# tritiled_v30_xpe.net
KiCad netlist of a schematic drawn in EAGLE
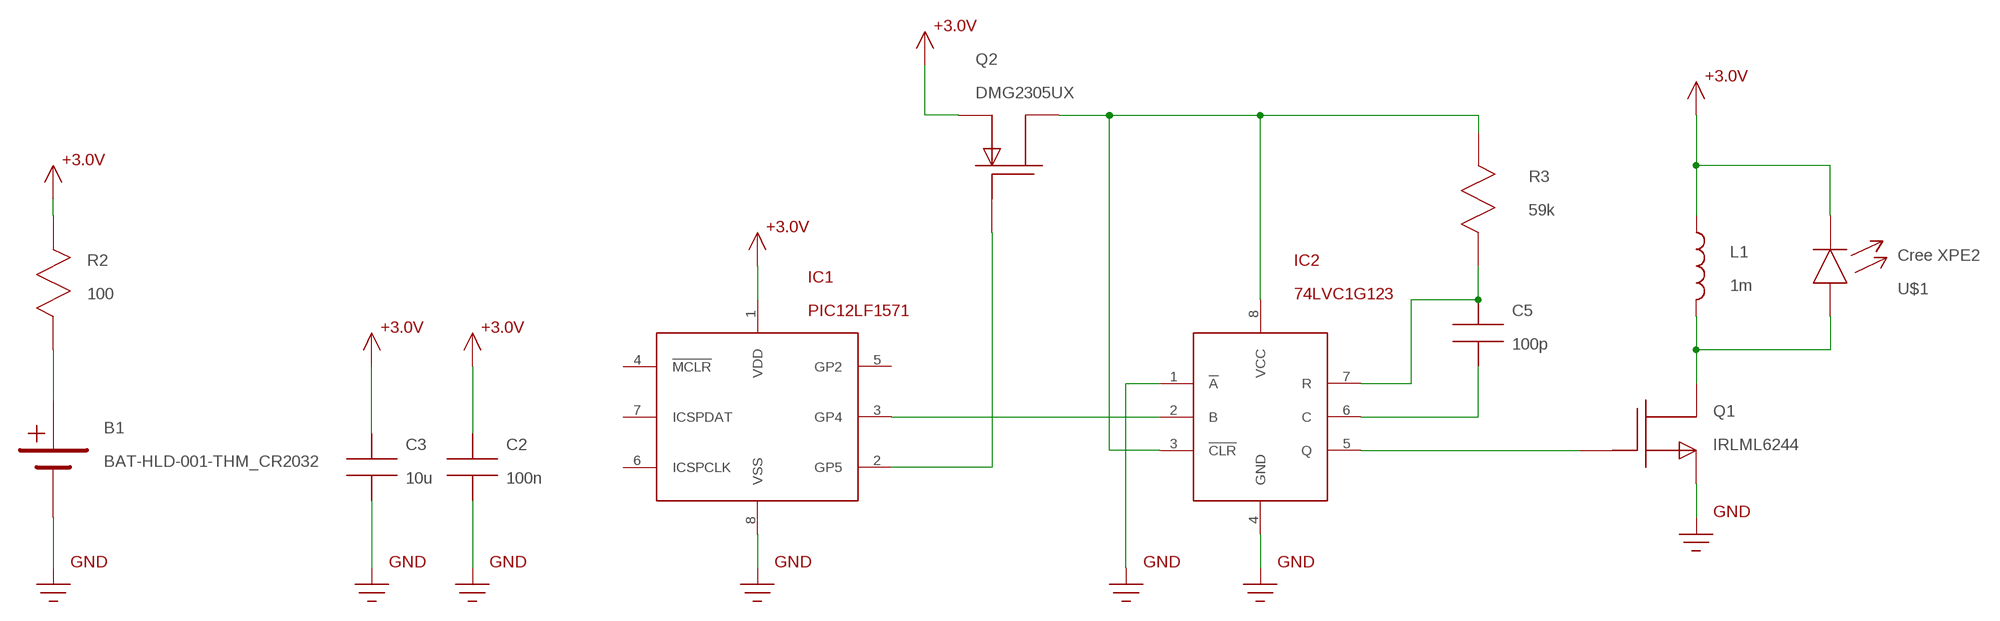
[diagram p0: schematic, sheet 1]

(export (version "E")
  (design (tool "Eeschema 10.0.6"))
  (components
    (comp (ref "B1")
      (value "BAT-HLD-001-THM_CR2032")
      (footprint "eagle-import:CR2032_BAT-HLD-001-THM")
      (libsource (lib "eagle-import") (part "BAT-HLD-001-THM_CR2032"))
    )
    (comp (ref "C2")
      (value "100n")
      (footprint "eagle-import:0805")
      (libsource (lib "eagle-import") (part "C0805"))
    )
    (comp (ref "C3")
      (value "10u")
      (footprint "eagle-import:1206")
      (libsource (lib "eagle-import") (part "C1206"))
    )
    (comp (ref "C5")
      (value "100p")
      (footprint "eagle-import:C0603")
      (libsource (lib "eagle-import") (part "C0603"))
    )
    (comp (ref "IC1")
      (value "PIC12LF1571")
      (footprint "eagle-import:SOIC8")
      (libsource (lib "eagle-import") (part "PIC12LF1571"))
    )
    (comp (ref "IC2")
      (value "74LVC1G123")
      (footprint "eagle-import:SM8")
      (libsource (lib "eagle-import") (part "74LVC1G123"))
    )
    (comp (ref "L1")
      (value "1m")
      (footprint "eagle-import:SRR6028_INDUCTOR")
      (libsource (lib "eagle-import") (part "SRR6028_INDUCTOR"))
    )
    (comp (ref "Q1")
      (value "IRLML6244")
      (footprint "eagle-import:SOT-23")
      (libsource (lib "eagle-import") (part "ZXMN3B01FSOT23"))
    )
    (comp (ref "Q2")
      (value "DMG2305UX")
      (footprint "eagle-import:SOT-23")
      (libsource (lib "eagle-import") (part "DMG2305UXSOT23"))
    )
    (comp (ref "R2")
      (value "100")
      (footprint "eagle-import:R1206")
      (libsource (lib "eagle-import") (part "R1206"))
    )
    (comp (ref "R3")
      (value "59k")
      (footprint "eagle-import:R0603")
      (libsource (lib "eagle-import") (part "R0603"))
    )
    (comp (ref "U$1")
      (value "Cree XPE2")
      (footprint "eagle-import:CREE_XPE_LED")
      (libsource (lib "eagle-import") (part "LEDCREE_XPE"))
    )
  )
  (nets
    (net (code "1") (name "+3.0V") (class "Default")
      (node (ref "C2") (pin "P$1") (pinfunction "P$1_P$1") (pintype "bidirectional"))
      (node (ref "C3") (pin "P$1") (pinfunction "P$1_P$1") (pintype "bidirectional"))
      (node (ref "IC1") (pin "1") (pinfunction "VDD_1") (pintype "bidirectional"))
      (node (ref "L1") (pin "P$1") (pinfunction "1_P$1") (pintype "passive"))
      (node (ref "Q2") (pin "2") (pinfunction "S_2") (pintype "bidirectional"))
      (node (ref "R2") (pin "P$1") (pinfunction "P$1_P$1") (pintype "bidirectional"))
      (node (ref "U$1") (pin "C") (pinfunction "C_C") (pintype "bidirectional"))
    )
    (net (code "2") (name "GND") (class "Default")
      (node (ref "B1") (pin "GND") (pinfunction "0V_GND") (pintype "power_in"))
      (node (ref "C2") (pin "P$2") (pinfunction "P$2_P$2") (pintype "bidirectional"))
      (node (ref "C3") (pin "P$2") (pinfunction "P$2_P$2") (pintype "bidirectional"))
      (node (ref "IC1") (pin "8") (pinfunction "VSS_8") (pintype "bidirectional"))
      (node (ref "IC2") (pin "1") (pinfunction "~{A}_1") (pintype "bidirectional"))
      (node (ref "IC2") (pin "4") (pinfunction "GND_4") (pintype "bidirectional"))
      (node (ref "Q1") (pin "2") (pinfunction "S_2") (pintype "bidirectional"))
    )
    (net (code "3") (name "Net-(B1-+V-Pad+V@1)") (class "Default")
      (node (ref "B1") (pin "+V@1") (pinfunction "+V_+V@1") (pintype "power_in"))
      (node (ref "B1") (pin "+V@2") (pinfunction "+V_+V@2") (pintype "power_in"))
      (node (ref "B1") (pin "+V@3") (pinfunction "+V_+V@3") (pintype "power_in"))
      (node (ref "B1") (pin "+V@4") (pinfunction "+V_+V@4") (pintype "power_in"))
      (node (ref "R2") (pin "P$2") (pinfunction "P$2_P$2") (pintype "bidirectional"))
    )
    (net (code "4") (name "Net-(IC1-GP4)") (class "Default")
      (node (ref "IC1") (pin "3") (pinfunction "GP4_3") (pintype "bidirectional"))
      (node (ref "IC2") (pin "2") (pinfunction "B_2") (pintype "bidirectional"))
    )
    (net (code "5") (name "Net-(IC1-GP5)") (class "Default")
      (node (ref "IC1") (pin "2") (pinfunction "GP5_2") (pintype "bidirectional"))
      (node (ref "Q2") (pin "1") (pinfunction "G_1") (pintype "bidirectional"))
    )
    (net (code "6") (name "Net-(IC2-C)") (class "Default")
      (node (ref "C5") (pin "P$2") (pinfunction "P$2_P$2") (pintype "bidirectional"))
      (node (ref "IC2") (pin "6") (pinfunction "C_6") (pintype "bidirectional"))
    )
    (net (code "7") (name "Net-(IC2-Q)") (class "Default")
      (node (ref "IC2") (pin "5") (pinfunction "Q_5") (pintype "bidirectional"))
      (node (ref "Q1") (pin "1") (pinfunction "G_1") (pintype "bidirectional"))
    )
    (net (code "8") (name "Net-(IC2-R)") (class "Default")
      (node (ref "C5") (pin "P$1") (pinfunction "P$1_P$1") (pintype "bidirectional"))
      (node (ref "IC2") (pin "7") (pinfunction "R_7") (pintype "bidirectional"))
      (node (ref "R3") (pin "P$1") (pinfunction "P$1_P$1") (pintype "bidirectional"))
    )
    (net (code "9") (name "Net-(IC2-VCC)") (class "Default")
      (node (ref "IC2") (pin "3") (pinfunction "~{CLR}_3") (pintype "bidirectional"))
      (node (ref "IC2") (pin "8") (pinfunction "VCC_8") (pintype "bidirectional"))
      (node (ref "Q2") (pin "3") (pinfunction "D_3") (pintype "bidirectional"))
      (node (ref "R3") (pin "P$2") (pinfunction "P$2_P$2") (pintype "bidirectional"))
    )
    (net (code "10") (name "Net-(L1-2)") (class "Default")
      (node (ref "L1") (pin "P$2") (pinfunction "2_P$2") (pintype "passive"))
      (node (ref "Q1") (pin "3") (pinfunction "D_3") (pintype "bidirectional"))
      (node (ref "U$1") (pin "A") (pinfunction "A_A") (pintype "bidirectional"))
    )
    (net (code "11") (name "unconnected-(IC1-GP2-Pad5)") (class "Default")
      (node (ref "IC1") (pin "5") (pinfunction "GP2_5") (pintype "bidirectional"))
    )
    (net (code "12") (name "unconnected-(IC1-ICSPCLK-Pad6)") (class "Default")
      (node (ref "IC1") (pin "6") (pinfunction "ICSPCLK_6") (pintype "bidirectional"))
    )
    (net (code "13") (name "unconnected-(IC1-ICSPDAT-Pad7)") (class "Default")
      (node (ref "IC1") (pin "7") (pinfunction "ICSPDAT_7") (pintype "bidirectional"))
    )
    (net (code "14") (name "unconnected-(IC1-~{MCLR}-Pad4)") (class "Default")
      (node (ref "IC1") (pin "4") (pinfunction "~{MCLR}_4") (pintype "bidirectional"))
    )
  )
)
